# ETC_SCH_2025-07-03.net
KiCad netlist of a schematic drawn in EasyEDA
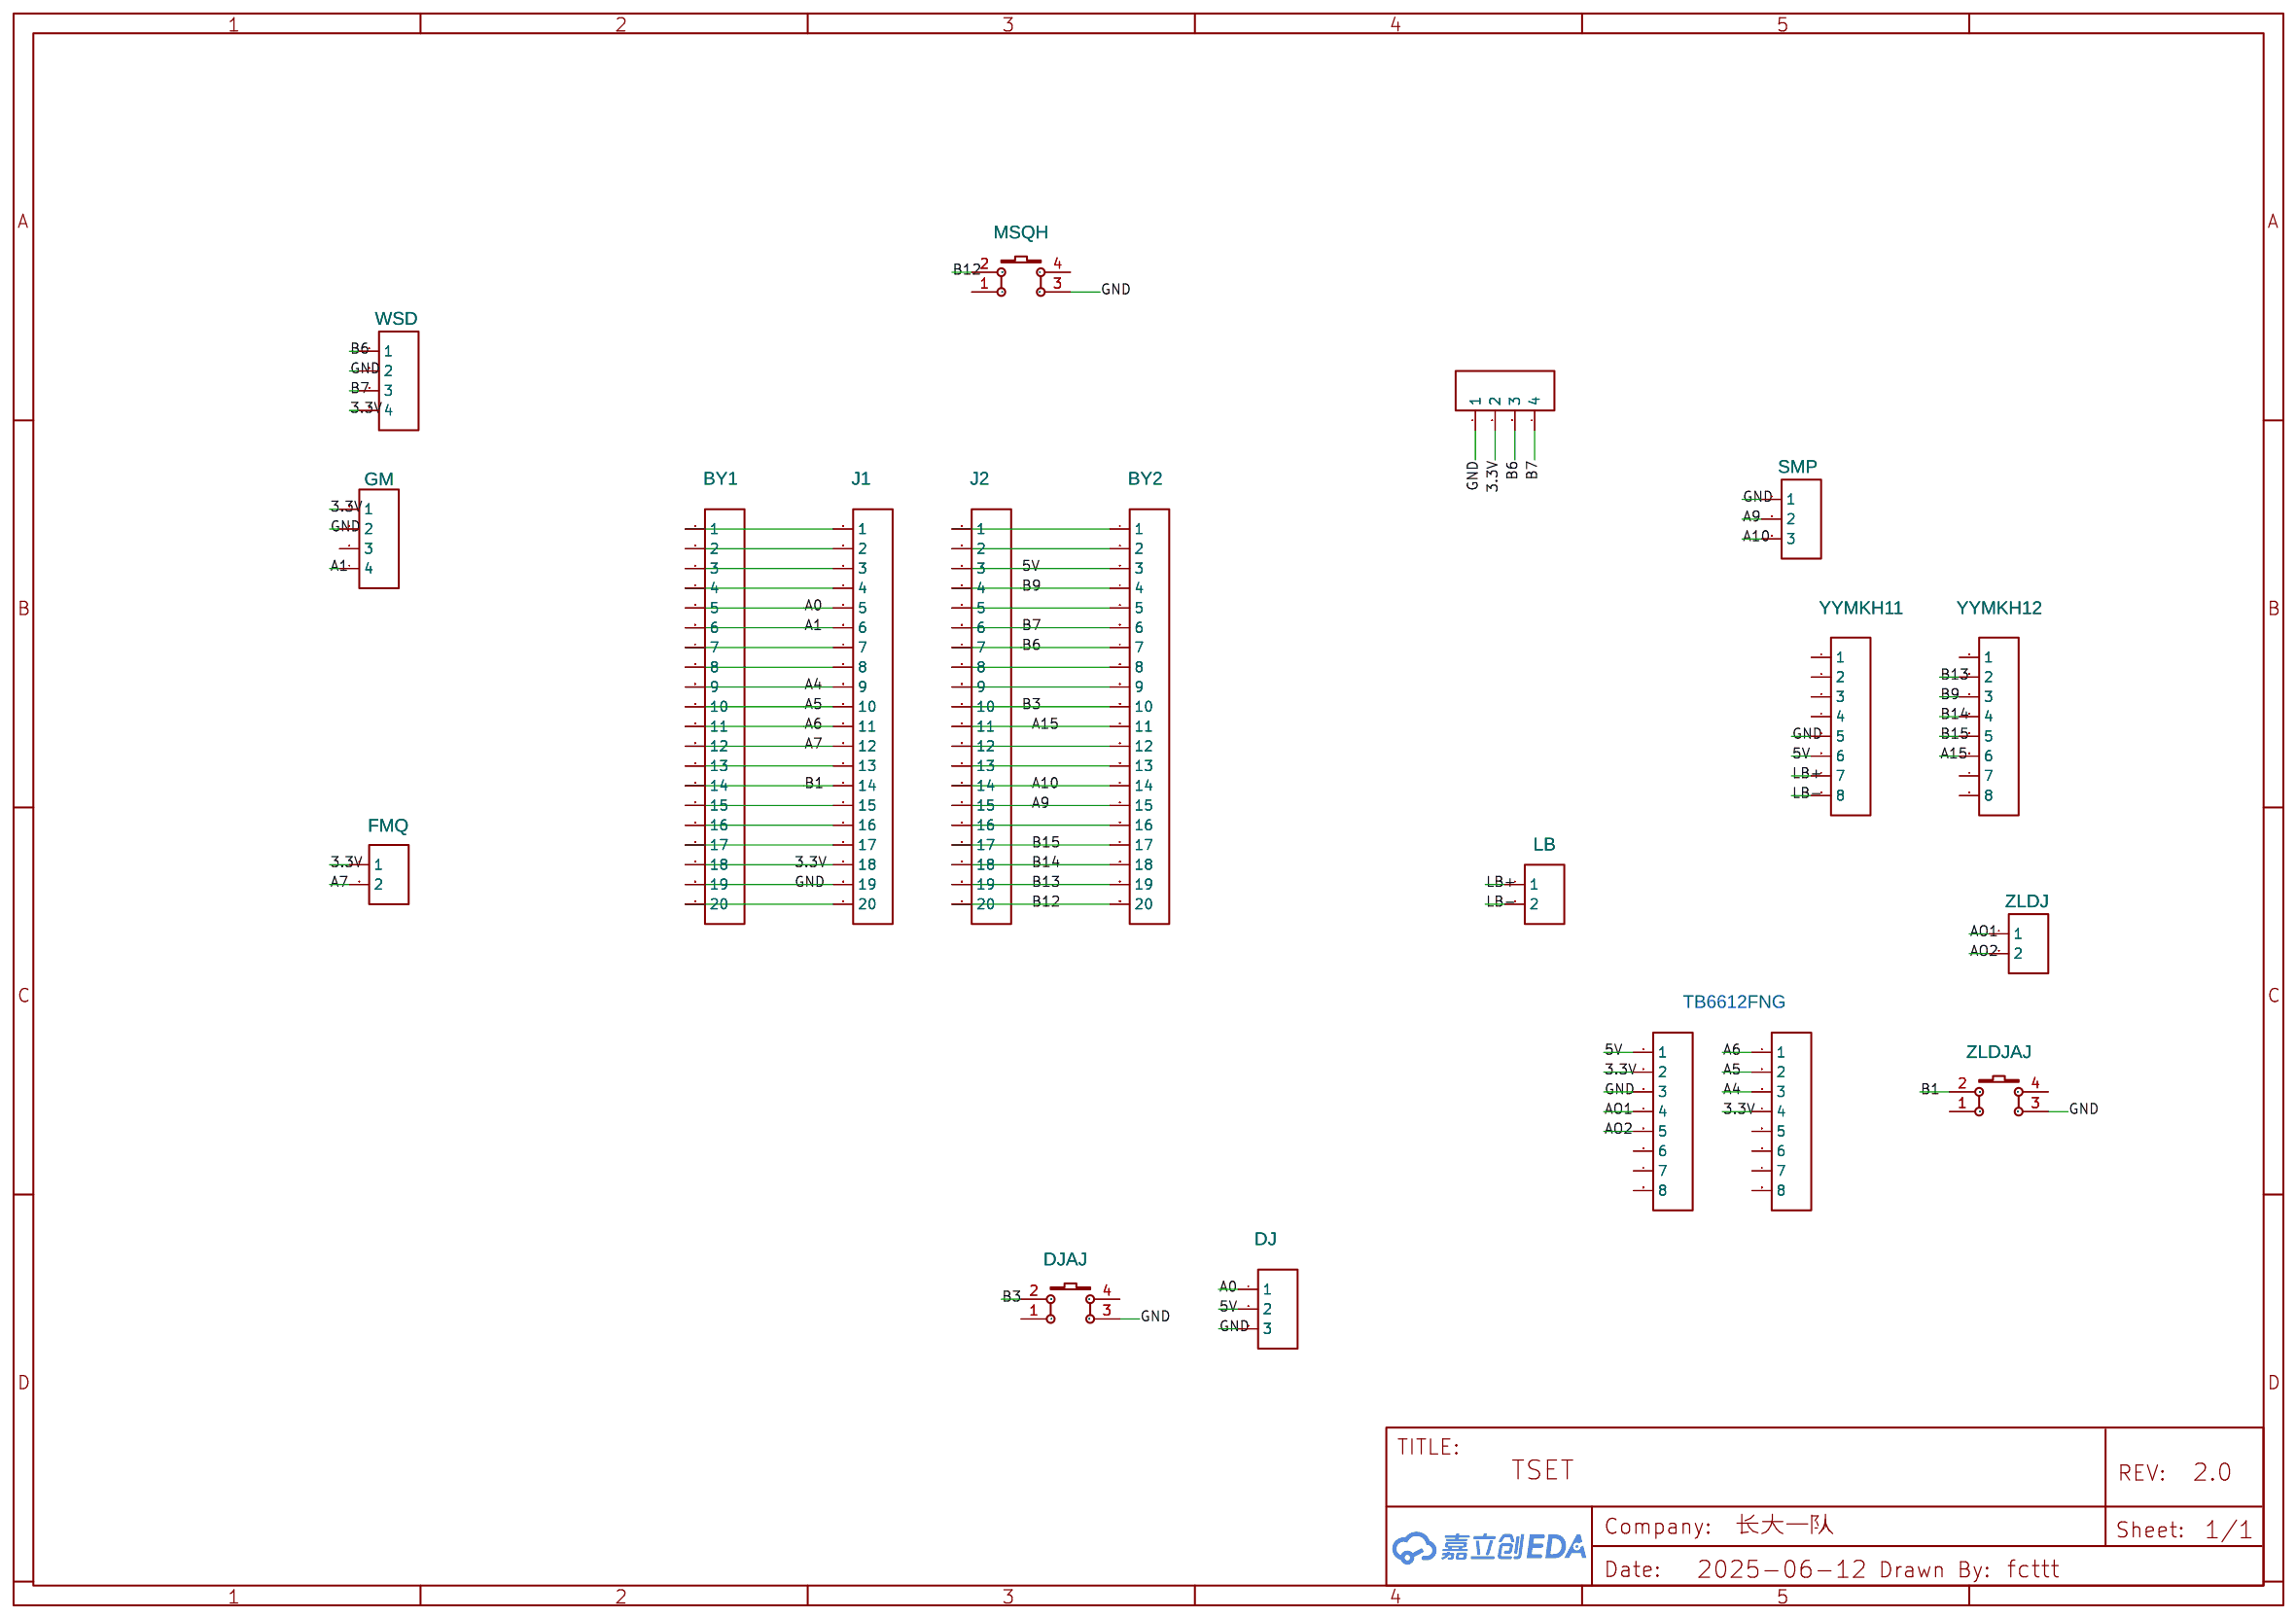
[diagram p0: schematic sheet]

(export (version "E")
  (design (tool "Eeschema 10.0.6"))
  (components
    (comp (ref "BY1") (value "HDR-M-2.54_1x20") (libsource (lib "") (part "HDR-M-2.54_1x20")))
    (comp (ref "BY2") (value "HDR-M-2.54_1x20") (libsource (lib "") (part "HDR-M-2.54_1x20")))
    (comp (ref "DJ") (value "HDR-F-2.54_1x3") (libsource (lib "") (part "HDR-F-2.54_1x3_1")))
    (comp (ref "DJAJ")
      (value "DJAJ")
      (fields (field (name "Manufacturer Part") "K2-1102DP-E4SW-04") (field (name "Manufacturer") "韩国韩荣"))
      (libsource (lib "") (part "K4-6×6_TH_1"))
    )
    (comp (ref "FMQ") (value "HDR-F-2.54_1x2") (libsource (lib "") (part "HDR-F-2.54_1x2_1")))
    (comp (ref "GM") (value "GM") (libsource (lib "") (part "HDR-F-2.54_1x4_1")))
    (comp (ref "J1") (value "HDR-M-2.54_1x20") (libsource (lib "") (part "HDR-M-2.54_1x20_1")))
    (comp (ref "J2") (value "HDR-M-2.54_1x20") (libsource (lib "") (part "HDR-M-2.54_1x20_1")))
    (comp (ref "LB") (value "HDR-F-2.54_1x2") (libsource (lib "") (part "HDR-F-2.54_1x2")))
    (comp (ref "MSQH")
      (value "K4-6×6_TH")
      (fields (field (name "Manufacturer Part") "K2-1102DP-E4SW-04") (field (name "Manufacturer") "韩国韩荣"))
      (libsource (lib "") (part "K4-6×6_TH_2"))
    )
    (comp (ref "OLED") (value "OLED") (libsource (lib "") (part "HDR-F-2.54_1x4")))
    (comp (ref "SMP") (value "SMP") (libsource (lib "") (part "HDR-F-2.54_1x3")))
    (comp (ref "TB6612H9") (value "HDR-F-2.54_1x8") (libsource (lib "") (part "HDR-F-2.54_1x8_1")))
    (comp (ref "TB6612H10") (value "HDR-F-2.54_1x8") (libsource (lib "") (part "HDR-F-2.54_1x8_1")))
    (comp (ref "WSD") (value "WSD") (libsource (lib "") (part "HDR-F-2.54_1x4_2")))
    (comp (ref "YYMKH11") (value "HDR-F-2.54_1x8") (libsource (lib "") (part "HDR-F-2.54_1x8")))
    (comp (ref "YYMKH12") (value "HDR-F-2.54_1x8") (libsource (lib "") (part "HDR-F-2.54_1x8")))
    (comp (ref "ZLDJ") (value "ZLDJ") (libsource (lib "") (part "HDR-F-2.54_1x2_2")))
    (comp (ref "ZLDJAJ")
      (value "K4-6×6_TH")
      (fields (field (name "Manufacturer Part") "K2-1102DP-E4SW-04") (field (name "Manufacturer") "韩国韩荣"))
      (libsource (lib "") (part "K4-6×6_TH"))
    )
  )
  (nets
    (net (code "1") (name "/3.3V") (class "Default")
      (node (ref "BY1") (pin "18") (pinfunction "18_18") (pintype "unspecified"))
      (node (ref "FMQ") (pin "1") (pinfunction "1_1") (pintype "input"))
      (node (ref "GM") (pin "1") (pinfunction "1_1") (pintype "unspecified"))
      (node (ref "J1") (pin "18") (pinfunction "18_18") (pintype "unspecified"))
      (node (ref "OLED") (pin "2") (pinfunction "2_2") (pintype "unspecified"))
      (node (ref "TB6612H10") (pin "4") (pinfunction "4_4") (pintype "unspecified"))
      (node (ref "TB6612H9") (pin "2") (pinfunction "2_2") (pintype "unspecified"))
      (node (ref "WSD") (pin "4") (pinfunction "4_4") (pintype "unspecified"))
    )
    (net (code "2") (name "/5V") (class "Default")
      (node (ref "BY2") (pin "3") (pinfunction "3_3") (pintype "unspecified"))
      (node (ref "DJ") (pin "2") (pinfunction "2_2") (pintype "input"))
      (node (ref "J2") (pin "3") (pinfunction "3_3") (pintype "unspecified"))
      (node (ref "TB6612H9") (pin "1") (pinfunction "1_1") (pintype "unspecified"))
      (node (ref "YYMKH11") (pin "6") (pinfunction "6_6") (pintype "unspecified"))
    )
    (net (code "3") (name "/A0") (class "Default")
      (node (ref "BY1") (pin "5") (pinfunction "5_5") (pintype "unspecified"))
      (node (ref "DJ") (pin "1") (pinfunction "1_1") (pintype "input"))
      (node (ref "J1") (pin "5") (pinfunction "5_5") (pintype "unspecified"))
    )
    (net (code "4") (name "/A1") (class "Default")
      (node (ref "BY1") (pin "6") (pinfunction "6_6") (pintype "unspecified"))
      (node (ref "GM") (pin "4") (pinfunction "4_4") (pintype "unspecified"))
      (node (ref "J1") (pin "6") (pinfunction "6_6") (pintype "unspecified"))
    )
    (net (code "5") (name "/A4") (class "Default")
      (node (ref "BY1") (pin "9") (pinfunction "9_9") (pintype "unspecified"))
      (node (ref "J1") (pin "9") (pinfunction "9_9") (pintype "unspecified"))
      (node (ref "TB6612H10") (pin "3") (pinfunction "3_3") (pintype "unspecified"))
    )
    (net (code "6") (name "/A5") (class "Default")
      (node (ref "BY1") (pin "10") (pinfunction "10_10") (pintype "unspecified"))
      (node (ref "J1") (pin "10") (pinfunction "10_10") (pintype "unspecified"))
      (node (ref "TB6612H10") (pin "2") (pinfunction "2_2") (pintype "unspecified"))
    )
    (net (code "7") (name "/A6") (class "Default")
      (node (ref "BY1") (pin "11") (pinfunction "11_11") (pintype "unspecified"))
      (node (ref "J1") (pin "11") (pinfunction "11_11") (pintype "unspecified"))
      (node (ref "TB6612H10") (pin "1") (pinfunction "1_1") (pintype "unspecified"))
    )
    (net (code "8") (name "/A7") (class "Default")
      (node (ref "BY1") (pin "12") (pinfunction "12_12") (pintype "unspecified"))
      (node (ref "FMQ") (pin "2") (pinfunction "2_2") (pintype "input"))
      (node (ref "J1") (pin "12") (pinfunction "12_12") (pintype "unspecified"))
    )
    (net (code "9") (name "/A9") (class "Default")
      (node (ref "BY2") (pin "15") (pinfunction "15_15") (pintype "unspecified"))
      (node (ref "J2") (pin "15") (pinfunction "15_15") (pintype "unspecified"))
      (node (ref "SMP") (pin "2") (pinfunction "2_2") (pintype "input"))
    )
    (net (code "10") (name "/A10") (class "Default")
      (node (ref "BY2") (pin "14") (pinfunction "14_14") (pintype "unspecified"))
      (node (ref "J2") (pin "14") (pinfunction "14_14") (pintype "unspecified"))
      (node (ref "SMP") (pin "3") (pinfunction "3_3") (pintype "input"))
    )
    (net (code "11") (name "/A15") (class "Default")
      (node (ref "BY2") (pin "11") (pinfunction "11_11") (pintype "unspecified"))
      (node (ref "J2") (pin "11") (pinfunction "11_11") (pintype "unspecified"))
      (node (ref "YYMKH12") (pin "6") (pinfunction "6_6") (pintype "unspecified"))
    )
    (net (code "12") (name "/AO1") (class "Default")
      (node (ref "TB6612H9") (pin "4") (pinfunction "4_4") (pintype "unspecified"))
      (node (ref "ZLDJ") (pin "1") (pinfunction "1_1") (pintype "input"))
    )
    (net (code "13") (name "/AO2") (class "Default")
      (node (ref "TB6612H9") (pin "5") (pinfunction "5_5") (pintype "unspecified"))
      (node (ref "ZLDJ") (pin "2") (pinfunction "2_2") (pintype "input"))
    )
    (net (code "14") (name "/B1") (class "Default")
      (node (ref "BY1") (pin "14") (pinfunction "14_14") (pintype "unspecified"))
      (node (ref "J1") (pin "14") (pinfunction "14_14") (pintype "unspecified"))
      (node (ref "ZLDJAJ") (pin "2") (pinfunction "2_2") (pintype "unspecified"))
    )
    (net (code "15") (name "/B3") (class "Default")
      (node (ref "BY2") (pin "10") (pinfunction "10_10") (pintype "unspecified"))
      (node (ref "DJAJ") (pin "2") (pinfunction "2_2") (pintype "unspecified"))
      (node (ref "J2") (pin "10") (pinfunction "10_10") (pintype "unspecified"))
    )
    (net (code "16") (name "/B6") (class "Default")
      (node (ref "BY2") (pin "7") (pinfunction "7_7") (pintype "unspecified"))
      (node (ref "J2") (pin "7") (pinfunction "7_7") (pintype "unspecified"))
      (node (ref "OLED") (pin "3") (pinfunction "3_3") (pintype "unspecified"))
      (node (ref "WSD") (pin "1") (pinfunction "1_1") (pintype "unspecified"))
    )
    (net (code "17") (name "/B7") (class "Default")
      (node (ref "BY2") (pin "6") (pinfunction "6_6") (pintype "unspecified"))
      (node (ref "J2") (pin "6") (pinfunction "6_6") (pintype "unspecified"))
      (node (ref "OLED") (pin "4") (pinfunction "4_4") (pintype "unspecified"))
      (node (ref "WSD") (pin "3") (pinfunction "3_3") (pintype "unspecified"))
    )
    (net (code "18") (name "/B9") (class "Default")
      (node (ref "BY2") (pin "4") (pinfunction "4_4") (pintype "unspecified"))
      (node (ref "J2") (pin "4") (pinfunction "4_4") (pintype "unspecified"))
      (node (ref "YYMKH12") (pin "3") (pinfunction "3_3") (pintype "unspecified"))
    )
    (net (code "19") (name "/B12") (class "Default")
      (node (ref "BY2") (pin "20") (pinfunction "20_20") (pintype "unspecified"))
      (node (ref "J2") (pin "20") (pinfunction "20_20") (pintype "unspecified"))
      (node (ref "MSQH") (pin "2") (pinfunction "2_2") (pintype "unspecified"))
    )
    (net (code "20") (name "/B13") (class "Default")
      (node (ref "BY2") (pin "19") (pinfunction "19_19") (pintype "unspecified"))
      (node (ref "J2") (pin "19") (pinfunction "19_19") (pintype "unspecified"))
      (node (ref "YYMKH12") (pin "2") (pinfunction "2_2") (pintype "unspecified"))
    )
    (net (code "21") (name "/B14") (class "Default")
      (node (ref "BY2") (pin "18") (pinfunction "18_18") (pintype "unspecified"))
      (node (ref "J2") (pin "18") (pinfunction "18_18") (pintype "unspecified"))
      (node (ref "YYMKH12") (pin "4") (pinfunction "4_4") (pintype "unspecified"))
    )
    (net (code "22") (name "/B15") (class "Default")
      (node (ref "BY2") (pin "17") (pinfunction "17_17") (pintype "unspecified"))
      (node (ref "J2") (pin "17") (pinfunction "17_17") (pintype "unspecified"))
      (node (ref "YYMKH12") (pin "5") (pinfunction "5_5") (pintype "unspecified"))
    )
    (net (code "23") (name "/GND") (class "Default")
      (node (ref "BY1") (pin "19") (pinfunction "19_19") (pintype "unspecified"))
      (node (ref "DJ") (pin "3") (pinfunction "3_3") (pintype "input"))
      (node (ref "DJAJ") (pin "3") (pinfunction "3_3") (pintype "unspecified"))
      (node (ref "GM") (pin "2") (pinfunction "2_2") (pintype "unspecified"))
      (node (ref "J1") (pin "19") (pinfunction "19_19") (pintype "unspecified"))
      (node (ref "MSQH") (pin "3") (pinfunction "3_3") (pintype "unspecified"))
      (node (ref "OLED") (pin "1") (pinfunction "1_1") (pintype "unspecified"))
      (node (ref "SMP") (pin "1") (pinfunction "1_1") (pintype "input"))
      (node (ref "TB6612H9") (pin "3") (pinfunction "3_3") (pintype "unspecified"))
      (node (ref "WSD") (pin "2") (pinfunction "2_2") (pintype "unspecified"))
      (node (ref "YYMKH11") (pin "5") (pinfunction "5_5") (pintype "unspecified"))
      (node (ref "ZLDJAJ") (pin "3") (pinfunction "3_3") (pintype "unspecified"))
    )
    (net (code "24") (name "/LB+") (class "Default")
      (node (ref "LB") (pin "1") (pinfunction "1_1") (pintype "input"))
      (node (ref "YYMKH11") (pin "7") (pinfunction "7_7") (pintype "unspecified"))
    )
    (net (code "25") (name "/LB-") (class "Default")
      (node (ref "LB") (pin "2") (pinfunction "2_2") (pintype "input"))
      (node (ref "YYMKH11") (pin "8") (pinfunction "8_8") (pintype "unspecified"))
    )
    (net (code "26") (name "Net-(BY1-Pad1)") (class "Default")
      (node (ref "BY1") (pin "1") (pinfunction "1_1") (pintype "unspecified"))
      (node (ref "J1") (pin "1") (pinfunction "1_1") (pintype "unspecified"))
    )
    (net (code "27") (name "Net-(BY1-Pad2)") (class "Default")
      (node (ref "BY1") (pin "2") (pinfunction "2_2") (pintype "unspecified"))
      (node (ref "J1") (pin "2") (pinfunction "2_2") (pintype "unspecified"))
    )
    (net (code "28") (name "Net-(BY1-Pad3)") (class "Default")
      (node (ref "BY1") (pin "3") (pinfunction "3_3") (pintype "unspecified"))
      (node (ref "J1") (pin "3") (pinfunction "3_3") (pintype "unspecified"))
    )
    (net (code "29") (name "Net-(BY1-Pad4)") (class "Default")
      (node (ref "BY1") (pin "4") (pinfunction "4_4") (pintype "unspecified"))
      (node (ref "J1") (pin "4") (pinfunction "4_4") (pintype "unspecified"))
    )
    (net (code "30") (name "Net-(BY1-Pad7)") (class "Default")
      (node (ref "BY1") (pin "7") (pinfunction "7_7") (pintype "unspecified"))
      (node (ref "J1") (pin "7") (pinfunction "7_7") (pintype "unspecified"))
    )
    (net (code "31") (name "Net-(BY1-Pad8)") (class "Default")
      (node (ref "BY1") (pin "8") (pinfunction "8_8") (pintype "unspecified"))
      (node (ref "J1") (pin "8") (pinfunction "8_8") (pintype "unspecified"))
    )
    (net (code "32") (name "Net-(BY1-Pad13)") (class "Default")
      (node (ref "BY1") (pin "13") (pinfunction "13_13") (pintype "unspecified"))
      (node (ref "J1") (pin "13") (pinfunction "13_13") (pintype "unspecified"))
    )
    (net (code "33") (name "Net-(BY1-Pad15)") (class "Default")
      (node (ref "BY1") (pin "15") (pinfunction "15_15") (pintype "unspecified"))
      (node (ref "J1") (pin "15") (pinfunction "15_15") (pintype "unspecified"))
    )
    (net (code "34") (name "Net-(BY1-Pad16)") (class "Default")
      (node (ref "BY1") (pin "16") (pinfunction "16_16") (pintype "unspecified"))
      (node (ref "J1") (pin "16") (pinfunction "16_16") (pintype "unspecified"))
    )
    (net (code "35") (name "Net-(BY1-Pad17)") (class "Default")
      (node (ref "BY1") (pin "17") (pinfunction "17_17") (pintype "unspecified"))
      (node (ref "J1") (pin "17") (pinfunction "17_17") (pintype "unspecified"))
    )
    (net (code "36") (name "Net-(BY1-Pad20)") (class "Default")
      (node (ref "BY1") (pin "20") (pinfunction "20_20") (pintype "unspecified"))
      (node (ref "J1") (pin "20") (pinfunction "20_20") (pintype "unspecified"))
    )
    (net (code "37") (name "Net-(BY2-Pad1)") (class "Default")
      (node (ref "BY2") (pin "1") (pinfunction "1_1") (pintype "unspecified"))
      (node (ref "J2") (pin "1") (pinfunction "1_1") (pintype "unspecified"))
    )
    (net (code "38") (name "Net-(BY2-Pad2)") (class "Default")
      (node (ref "BY2") (pin "2") (pinfunction "2_2") (pintype "unspecified"))
      (node (ref "J2") (pin "2") (pinfunction "2_2") (pintype "unspecified"))
    )
    (net (code "39") (name "Net-(BY2-Pad5)") (class "Default")
      (node (ref "BY2") (pin "5") (pinfunction "5_5") (pintype "unspecified"))
      (node (ref "J2") (pin "5") (pinfunction "5_5") (pintype "unspecified"))
    )
    (net (code "40") (name "Net-(BY2-Pad8)") (class "Default")
      (node (ref "BY2") (pin "8") (pinfunction "8_8") (pintype "unspecified"))
      (node (ref "J2") (pin "8") (pinfunction "8_8") (pintype "unspecified"))
    )
    (net (code "41") (name "Net-(BY2-Pad9)") (class "Default")
      (node (ref "BY2") (pin "9") (pinfunction "9_9") (pintype "unspecified"))
      (node (ref "J2") (pin "9") (pinfunction "9_9") (pintype "unspecified"))
    )
    (net (code "42") (name "Net-(BY2-Pad12)") (class "Default")
      (node (ref "BY2") (pin "12") (pinfunction "12_12") (pintype "unspecified"))
      (node (ref "J2") (pin "12") (pinfunction "12_12") (pintype "unspecified"))
    )
    (net (code "43") (name "Net-(BY2-Pad13)") (class "Default")
      (node (ref "BY2") (pin "13") (pinfunction "13_13") (pintype "unspecified"))
      (node (ref "J2") (pin "13") (pinfunction "13_13") (pintype "unspecified"))
    )
    (net (code "44") (name "Net-(BY2-Pad16)") (class "Default")
      (node (ref "BY2") (pin "16") (pinfunction "16_16") (pintype "unspecified"))
      (node (ref "J2") (pin "16") (pinfunction "16_16") (pintype "unspecified"))
    )
    (net (code "45") (name "unconnected-(DJAJ-Pad1)") (class "Default")
      (node (ref "DJAJ") (pin "1") (pinfunction "1_1") (pintype "unspecified"))
    )
    (net (code "46") (name "unconnected-(DJAJ-Pad4)") (class "Default")
      (node (ref "DJAJ") (pin "4") (pinfunction "4_4") (pintype "unspecified"))
    )
    (net (code "47") (name "unconnected-(GM-Pad3)") (class "Default")
      (node (ref "GM") (pin "3") (pinfunction "3_3") (pintype "unspecified"))
    )
    (net (code "48") (name "unconnected-(MSQH-Pad1)") (class "Default")
      (node (ref "MSQH") (pin "1") (pinfunction "1_1") (pintype "unspecified"))
    )
    (net (code "49") (name "unconnected-(MSQH-Pad4)") (class "Default")
      (node (ref "MSQH") (pin "4") (pinfunction "4_4") (pintype "unspecified"))
    )
    (net (code "50") (name "unconnected-(TB6612H9-Pad6)") (class "Default")
      (node (ref "TB6612H9") (pin "6") (pinfunction "6_6") (pintype "unspecified"))
    )
    (net (code "51") (name "unconnected-(TB6612H9-Pad7)") (class "Default")
      (node (ref "TB6612H9") (pin "7") (pinfunction "7_7") (pintype "unspecified"))
    )
    (net (code "52") (name "unconnected-(TB6612H9-Pad8)") (class "Default")
      (node (ref "TB6612H9") (pin "8") (pinfunction "8_8") (pintype "unspecified"))
    )
    (net (code "53") (name "unconnected-(TB6612H10-Pad5)") (class "Default")
      (node (ref "TB6612H10") (pin "5") (pinfunction "5_5") (pintype "unspecified"))
    )
    (net (code "54") (name "unconnected-(TB6612H10-Pad6)") (class "Default")
      (node (ref "TB6612H10") (pin "6") (pinfunction "6_6") (pintype "unspecified"))
    )
    (net (code "55") (name "unconnected-(TB6612H10-Pad7)") (class "Default")
      (node (ref "TB6612H10") (pin "7") (pinfunction "7_7") (pintype "unspecified"))
    )
    (net (code "56") (name "unconnected-(TB6612H10-Pad8)") (class "Default")
      (node (ref "TB6612H10") (pin "8") (pinfunction "8_8") (pintype "unspecified"))
    )
    (net (code "57") (name "unconnected-(YYMKH11-Pad1)") (class "Default")
      (node (ref "YYMKH11") (pin "1") (pinfunction "1_1") (pintype "unspecified"))
    )
    (net (code "58") (name "unconnected-(YYMKH11-Pad2)") (class "Default")
      (node (ref "YYMKH11") (pin "2") (pinfunction "2_2") (pintype "unspecified"))
    )
    (net (code "59") (name "unconnected-(YYMKH11-Pad3)") (class "Default")
      (node (ref "YYMKH11") (pin "3") (pinfunction "3_3") (pintype "unspecified"))
    )
    (net (code "60") (name "unconnected-(YYMKH11-Pad4)") (class "Default")
      (node (ref "YYMKH11") (pin "4") (pinfunction "4_4") (pintype "unspecified"))
    )
    (net (code "61") (name "unconnected-(YYMKH12-Pad1)") (class "Default")
      (node (ref "YYMKH12") (pin "1") (pinfunction "1_1") (pintype "unspecified"))
    )
    (net (code "62") (name "unconnected-(YYMKH12-Pad7)") (class "Default")
      (node (ref "YYMKH12") (pin "7") (pinfunction "7_7") (pintype "unspecified"))
    )
    (net (code "63") (name "unconnected-(YYMKH12-Pad8)") (class "Default")
      (node (ref "YYMKH12") (pin "8") (pinfunction "8_8") (pintype "unspecified"))
    )
    (net (code "64") (name "unconnected-(ZLDJAJ-Pad1)") (class "Default")
      (node (ref "ZLDJAJ") (pin "1") (pinfunction "1_1") (pintype "unspecified"))
    )
    (net (code "65") (name "unconnected-(ZLDJAJ-Pad4)") (class "Default")
      (node (ref "ZLDJAJ") (pin "4") (pinfunction "4_4") (pintype "unspecified"))
    )
  )
)
